# coop_assistant.net
KiCad netlist of a schematic drawn in EAGLE
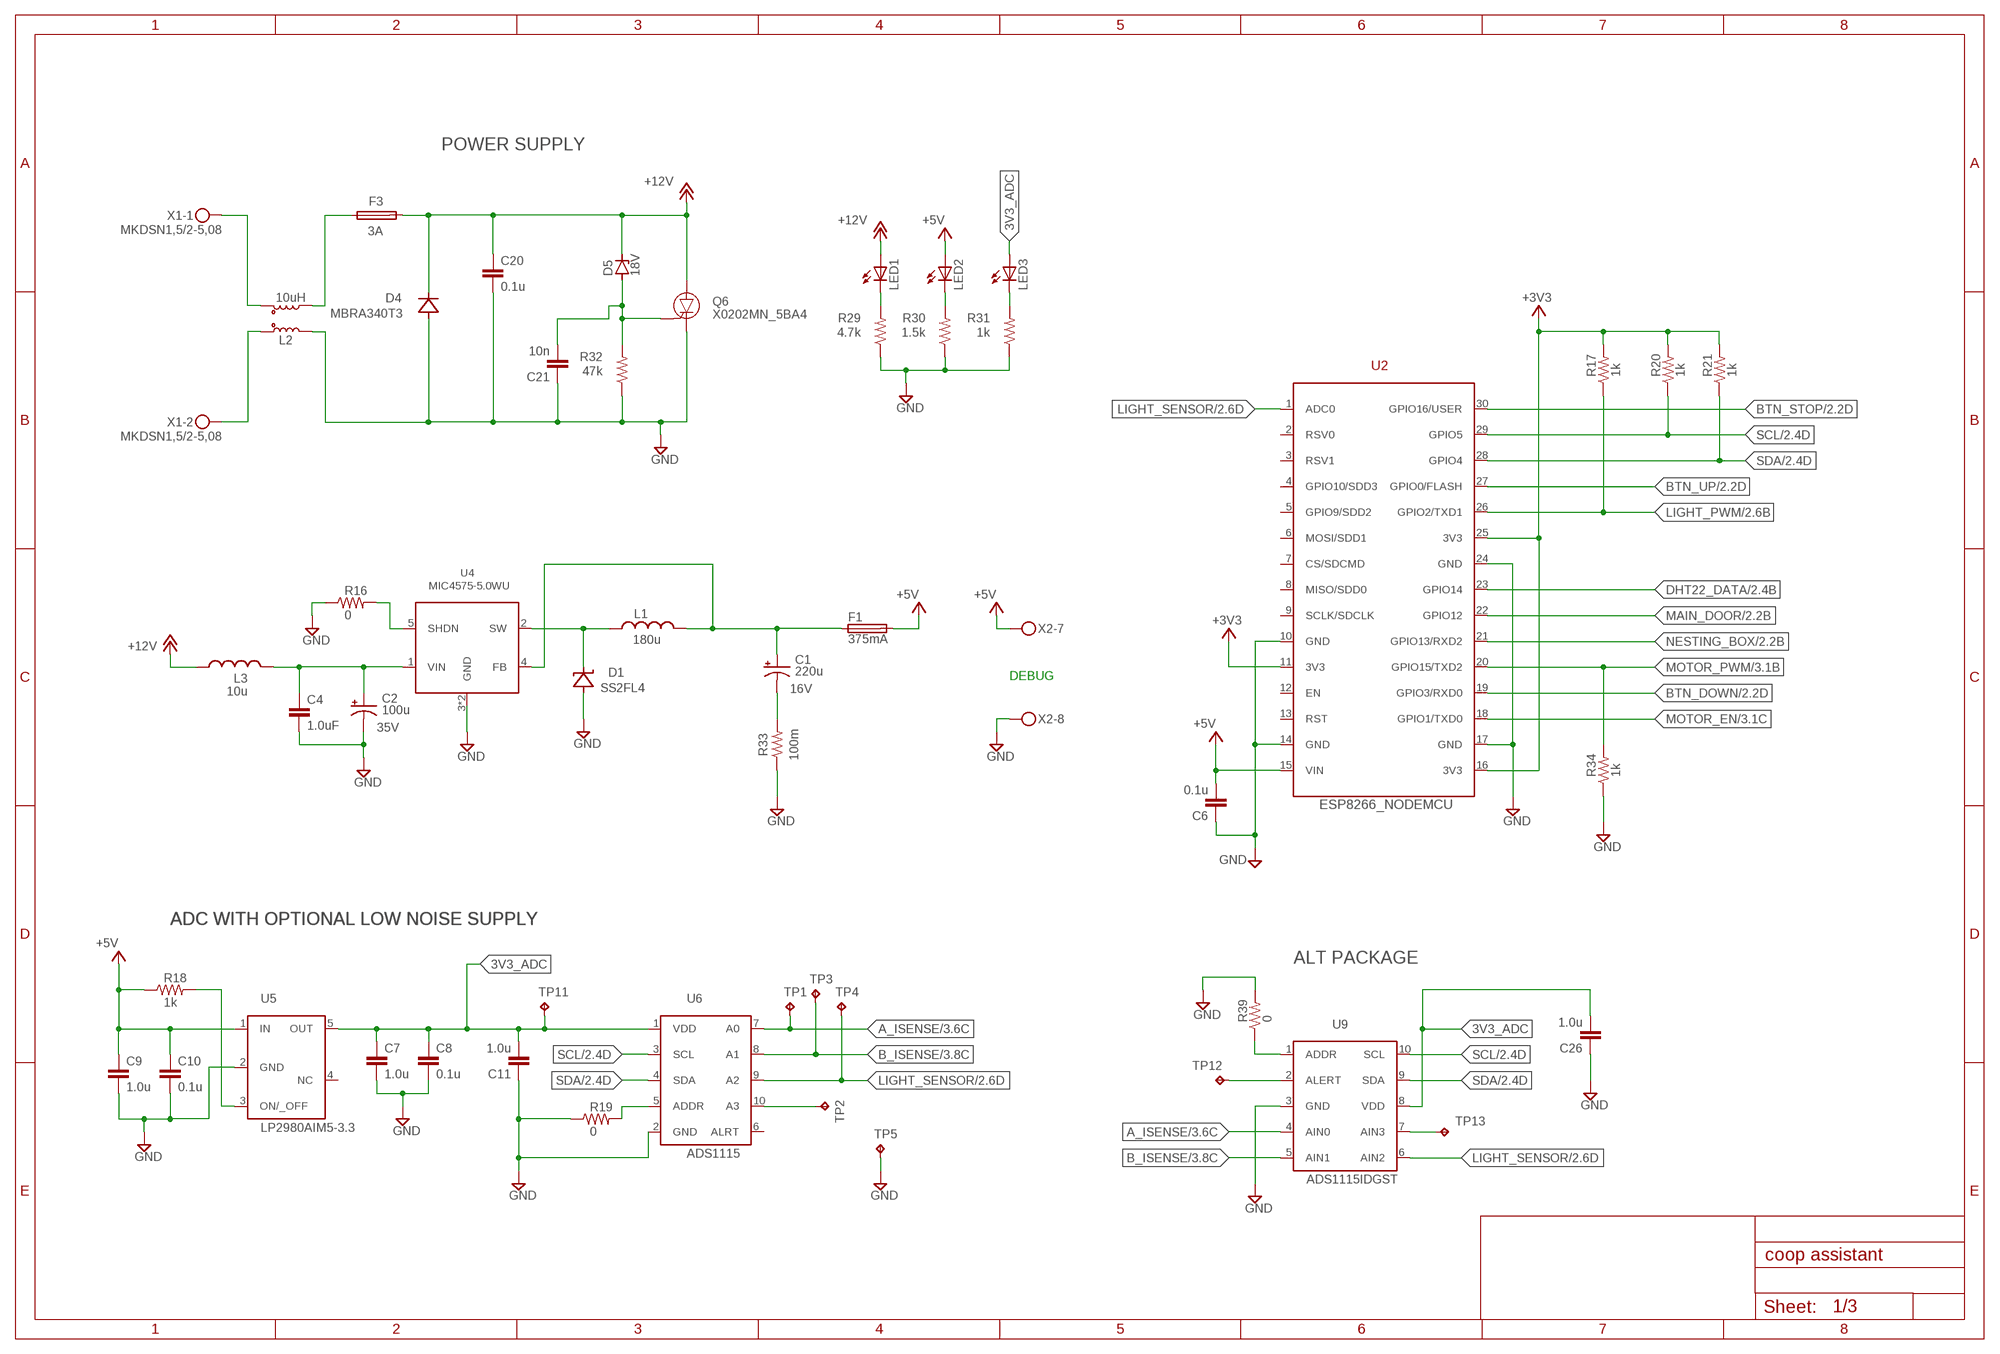
[diagram p0: schematic, sheet 1]
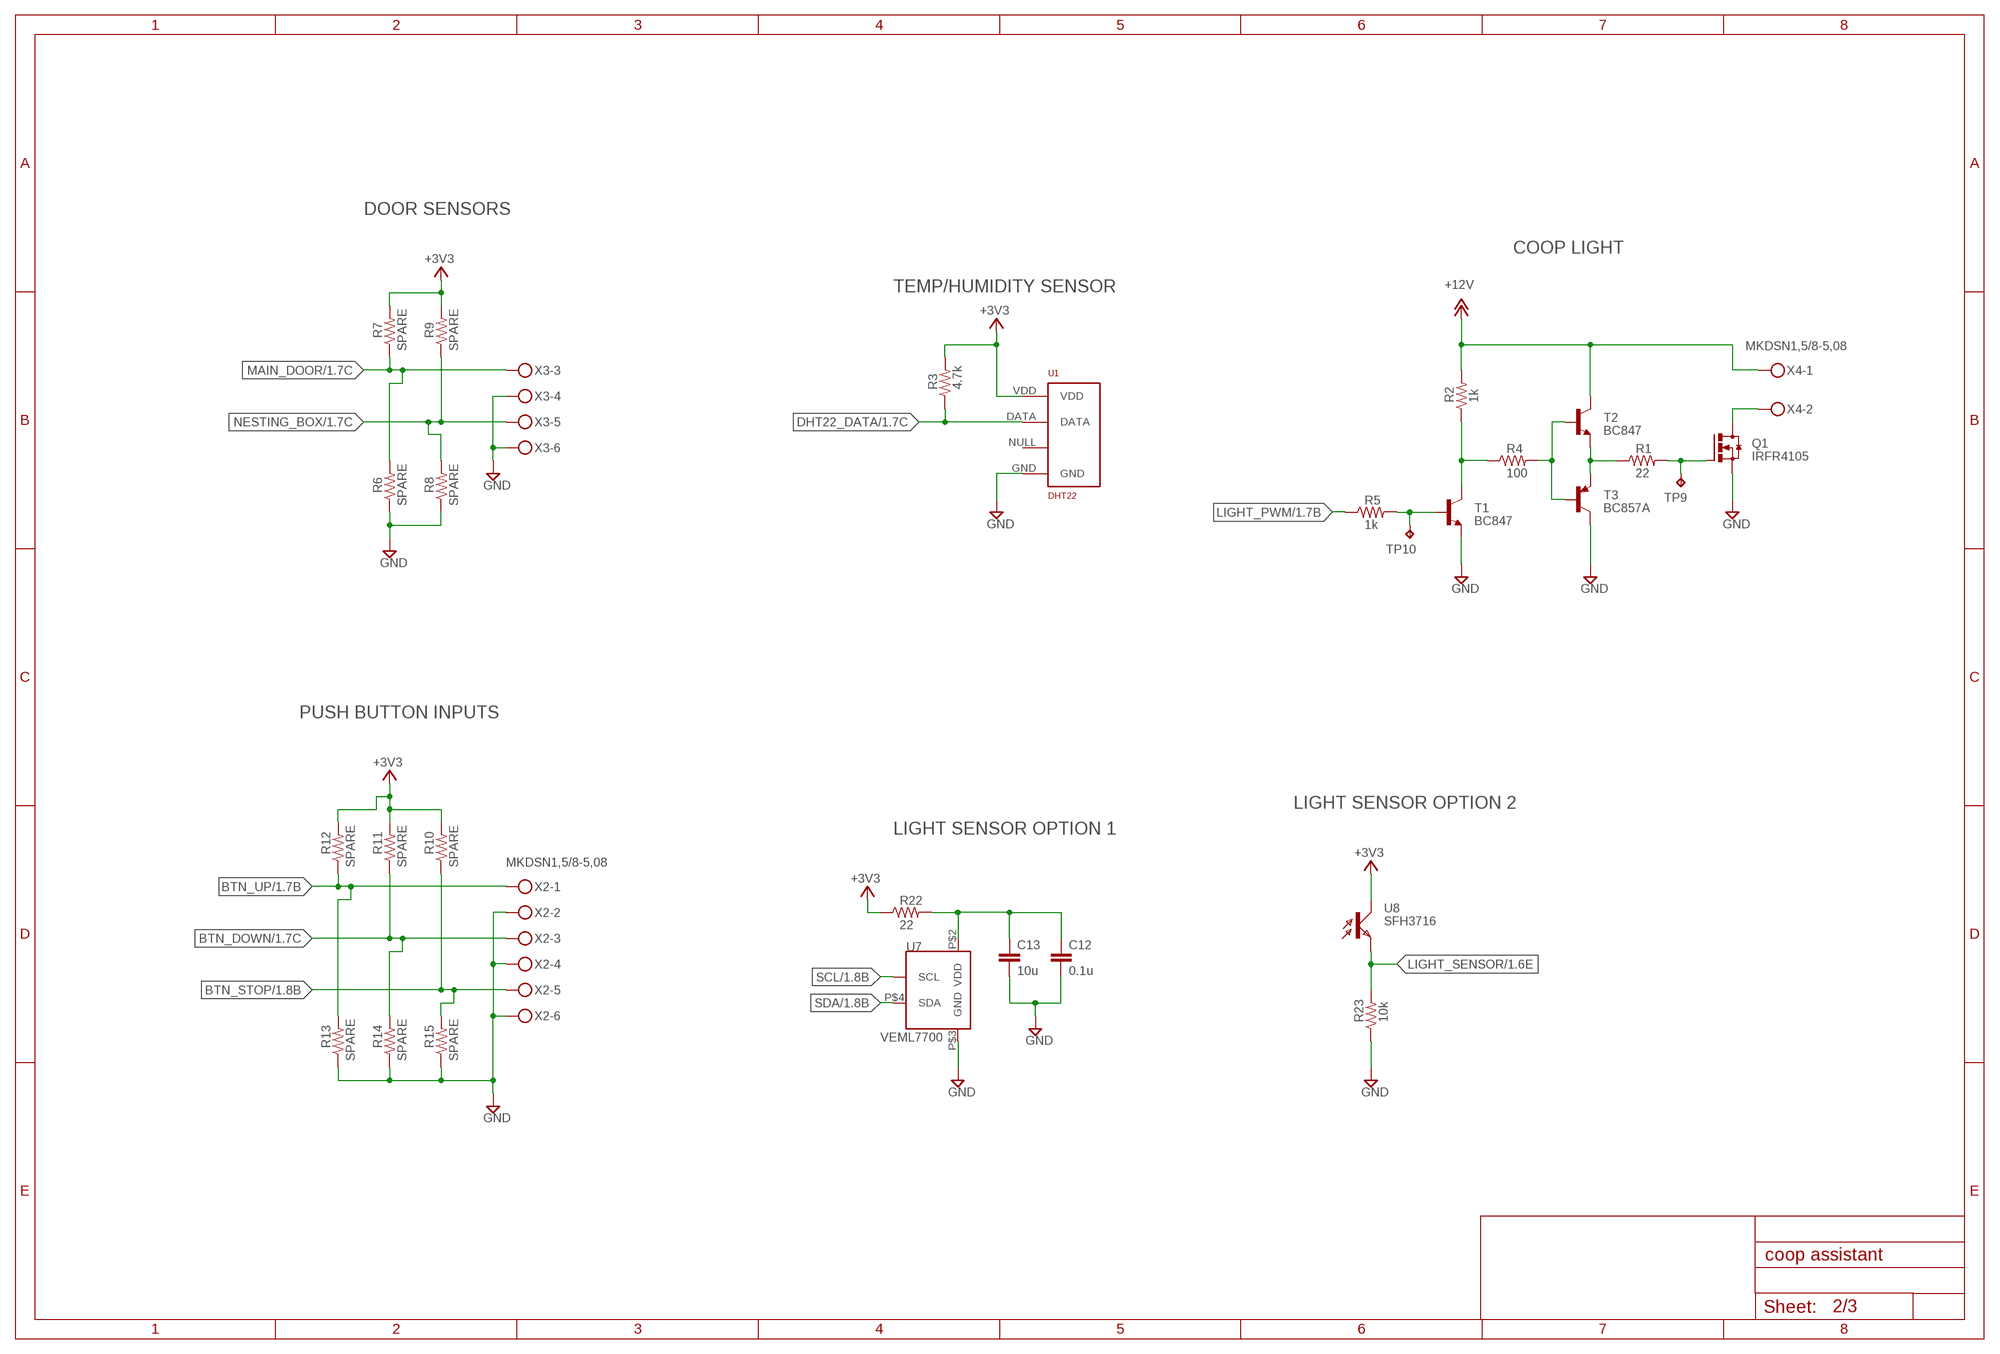
[diagram p1: schematic, sheet 2]
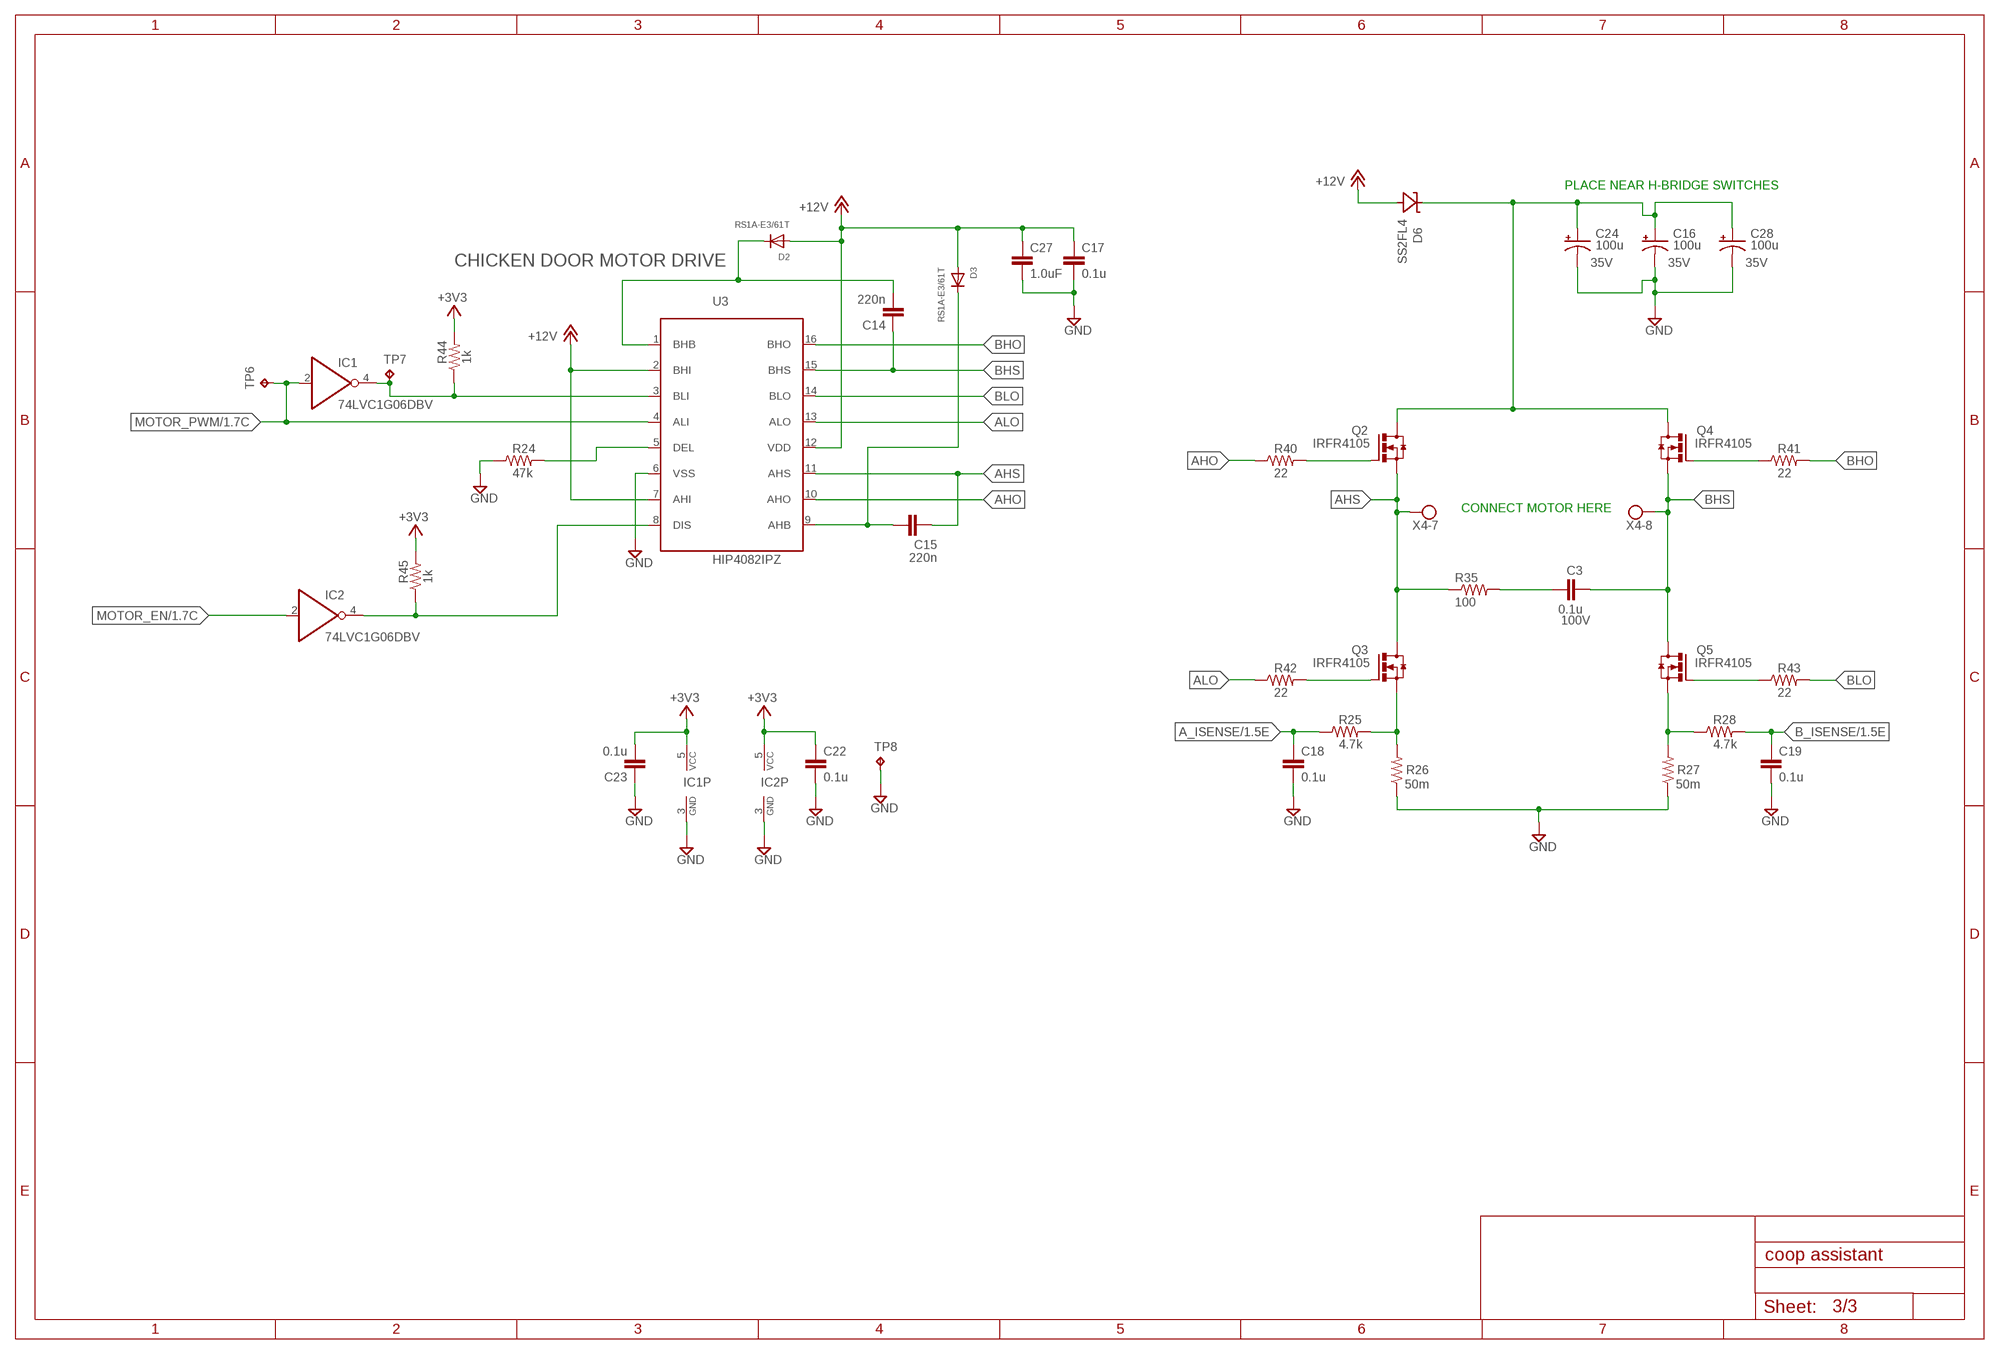
[diagram p2: schematic, sheet 3]

(export (version "E")
  (design (tool "Eeschema 10.0.6"))
  (components
    (comp (ref "C1")
      (value "220u")
      (footprint "eagle-import:CAPPRD250W50D630H800B")
      (fields (field (name "VOLTAGE") "16V"))
      (libsource (lib "eagle-import") (part "CPOLRAD6.3X8"))
    )
    (comp (ref "C2")
      (value "100u")
      (footprint "eagle-import:CAPPRD350W60D800H1200B")
      (fields (field (name "VOLTAGE") "35V"))
      (libsource (lib "eagle-import") (part "CPOLRAD8X12"))
    )
    (comp (ref "C4")
      (value "1.0uF")
      (footprint "eagle-import:0805")
      (libsource (lib "eagle-import") (part "1.0UF-0805-25V-10%"))
    )
    (comp (ref "C6")
      (value "0.1u")
      (footprint "eagle-import:0603")
      (libsource (lib "eagle-import") (part "1.0UF-0603-16V-10%"))
    )
    (comp (ref "C7")
      (value "1.0u")
      (footprint "eagle-import:0805")
      (libsource (lib "eagle-import") (part "1.0UF-0805-25V-10%"))
    )
    (comp (ref "C8")
      (value "0.1u")
      (footprint "eagle-import:0603")
      (libsource (lib "eagle-import") (part "1.0UF-0603-16V-10%"))
    )
    (comp (ref "C9")
      (value "1.0u")
      (footprint "eagle-import:0805")
      (libsource (lib "eagle-import") (part "1.0UF-0805-25V-10%"))
    )
    (comp (ref "C10")
      (value "0.1u")
      (footprint "eagle-import:0603")
      (libsource (lib "eagle-import") (part "1.0UF-0603-16V-10%"))
    )
    (comp (ref "C11")
      (value "1.0u")
      (footprint "eagle-import:0805")
      (libsource (lib "eagle-import") (part "1.0UF-0805-25V-10%"))
    )
    (comp (ref "C20")
      (value "0.1u")
      (footprint "eagle-import:C0805")
      (libsource (lib "eagle-import") (part "C-EUC0805"))
    )
    (comp (ref "C21")
      (value "10n")
      (footprint "eagle-import:C0805")
      (libsource (lib "eagle-import") (part "C-EUC0805"))
    )
    (comp (ref "C26")
      (value "1.0u")
      (footprint "eagle-import:0805")
      (libsource (lib "eagle-import") (part "1.0UF-0805-25V-10%"))
    )
    (comp (ref "D1")
      (value "SS2FL4")
      (footprint "eagle-import:SMF")
      (libsource (lib "eagle-import") (part "SS2FL4"))
    )
    (comp (ref "D4")
      (value "MBRA340T3")
      (footprint "eagle-import:SMA")
      (libsource (lib "eagle-import") (part "MBRA340T3"))
    )
    (comp (ref "D5")
      (value "18V")
      (footprint "eagle-import:SOT23")
      (libsource (lib "eagle-import") (part "ZENER-DIODESOT23"))
    )
    (comp (ref "F1")
      (value "375mA")
      (footprint "eagle-import:0603")
      (libsource (lib "eagle-import") (part "494SERIESFUSE"))
    )
    (comp (ref "F3")
      (value "3A")
      (footprint "eagle-import:FUSM9750X381N")
      (libsource (lib "eagle-import") (part "154_OMNIBLOKF154"))
    )
    (comp (ref "L1")
      (value "180u")
      (footprint "eagle-import:INDM120120X780N")
      (libsource (lib "eagle-import") (part "MSS1278"))
    )
    (comp (ref "L2")
      (value "10uH")
      (footprint "eagle-import:COILCRAFT_MSD1260")
      (libsource (lib "eagle-import") (part "COILCRAFT_MSD1260"))
    )
    (comp (ref "L3")
      (value "10u")
      (footprint "eagle-import:INDM120120X780N")
      (libsource (lib "eagle-import") (part "MSS1278"))
    )
    (comp (ref "LED1")
      (value "LEDCHIP-LED0805")
      (footprint "eagle-import:CHIP-LED0805")
      (libsource (lib "eagle-import") (part "LEDCHIP-LED0805"))
    )
    (comp (ref "LED2")
      (value "LEDCHIP-LED0805")
      (footprint "eagle-import:CHIP-LED0805")
      (libsource (lib "eagle-import") (part "LEDCHIP-LED0805"))
    )
    (comp (ref "LED3")
      (value "LEDCHIP-LED0805")
      (footprint "eagle-import:CHIP-LED0805")
      (libsource (lib "eagle-import") (part "LEDCHIP-LED0805"))
    )
    (comp (ref "Q6")
      (value "X0202MN_5BA4")
      (footprint "eagle-import:SOT-223")
      (fields
        (field (name "DIGIKEY_PARTNO") "497-2532-2-ND")
        (field (name "MANUFACTURER") "STMicroelectronics")
        (field (name "MPN") "X0202MN 5BA4")
        (field (name "CREATED_BY") "PCBLayout.com")
      )
      (libsource (lib "eagle-import") (part "X0202MN_5BA4"))
    )
    (comp (ref "R16")
      (value "0")
      (footprint "eagle-import:R0805")
      (libsource (lib "eagle-import") (part "R-US_R0805"))
    )
    (comp (ref "R17")
      (value "1k")
      (footprint "eagle-import:R0805")
      (libsource (lib "eagle-import") (part "R-US_R0805"))
    )
    (comp (ref "R18")
      (value "1k")
      (footprint "eagle-import:R0805")
      (libsource (lib "eagle-import") (part "R-US_R0805"))
    )
    (comp (ref "R19")
      (value "0")
      (footprint "eagle-import:R0805")
      (libsource (lib "eagle-import") (part "R-US_R0805"))
    )
    (comp (ref "R20")
      (value "1k")
      (footprint "eagle-import:R0805")
      (libsource (lib "eagle-import") (part "R-US_R0805"))
    )
    (comp (ref "R21")
      (value "1k")
      (footprint "eagle-import:R0805")
      (libsource (lib "eagle-import") (part "R-US_R0805"))
    )
    (comp (ref "R29")
      (value "4.7k")
      (footprint "eagle-import:R0805")
      (libsource (lib "eagle-import") (part "R-US_R0805"))
    )
    (comp (ref "R30")
      (value "1.5k")
      (footprint "eagle-import:R0805")
      (libsource (lib "eagle-import") (part "R-US_R0805"))
    )
    (comp (ref "R31")
      (value "1k")
      (footprint "eagle-import:R0805")
      (libsource (lib "eagle-import") (part "R-US_R0805"))
    )
    (comp (ref "R32")
      (value "47k")
      (footprint "eagle-import:R0805")
      (libsource (lib "eagle-import") (part "R-US_R0805"))
    )
    (comp (ref "R33")
      (value "100m")
      (footprint "eagle-import:RESC3216X70")
      (libsource (lib "eagle-import") (part "R-USCHIP-1206(3216-METRIC)_"))
    )
    (comp (ref "R34")
      (value "1k")
      (footprint "eagle-import:R0805")
      (libsource (lib "eagle-import") (part "R-US_R0805"))
    )
    (comp (ref "R39")
      (value "0")
      (footprint "eagle-import:R0805")
      (libsource (lib "eagle-import") (part "R-US_R0805"))
    )
    (comp (ref "TP1")
      (value "TPTP15SQ")
      (footprint "eagle-import:TP15SQ")
      (libsource (lib "eagle-import") (part "TPTP15SQ"))
    )
    (comp (ref "TP2")
      (value "TPTP15SQ")
      (footprint "eagle-import:TP15SQ")
      (libsource (lib "eagle-import") (part "TPTP15SQ"))
    )
    (comp (ref "TP3")
      (value "TPTP15SQ")
      (footprint "eagle-import:TP15SQ")
      (libsource (lib "eagle-import") (part "TPTP15SQ"))
    )
    (comp (ref "TP4")
      (value "TPTP15SQ")
      (footprint "eagle-import:TP15SQ")
      (libsource (lib "eagle-import") (part "TPTP15SQ"))
    )
    (comp (ref "TP5")
      (value "TPTP15SQ")
      (footprint "eagle-import:TP15SQ")
      (libsource (lib "eagle-import") (part "TPTP15SQ"))
    )
    (comp (ref "TP11")
      (value "TPTP15SQ")
      (footprint "eagle-import:TP15SQ")
      (libsource (lib "eagle-import") (part "TPTP15SQ"))
    )
    (comp (ref "TP12")
      (value "TPTP15SQ")
      (footprint "eagle-import:TP15SQ")
      (libsource (lib "eagle-import") (part "TPTP15SQ"))
    )
    (comp (ref "TP13")
      (value "TPTP15SQ")
      (footprint "eagle-import:TP15SQ")
      (libsource (lib "eagle-import") (part "TPTP15SQ"))
    )
    (comp (ref "U2")
      (value "ESP8266_NODEMCU")
      (footprint "eagle-import:NODEMCUESP8266")
      (libsource (lib "eagle-import") (part "ESP8266_NODEMCU"))
    )
    (comp (ref "U4")
      (value "MIC4575-5.0WU")
      (footprint "eagle-import:TO263-5")
      (libsource (lib "eagle-import") (part "MIC4575-5.0WU"))
    )
    (comp (ref "U5")
      (value "LP2980AIM5-3.3")
      (footprint "eagle-import:SOT23-5")
      (libsource (lib "eagle-import") (part "LP2980AIM5-3.3"))
    )
    (comp (ref "U6")
      (value "ADS1115")
      (footprint "eagle-import:HDRV10W64P254_1X10_2800X508X838B")
      (libsource (lib "eagle-import") (part "ADS1115"))
    )
    (comp (ref "U9")
      (value "ADS1115IDGST")
      (footprint "eagle-import:10VSSOP")
      (libsource (lib "eagle-import") (part "ADS1115IDGST"))
    )
    (comp (ref "X1")
      (value "MKDSN1,5/2-5,08")
      (footprint "eagle-import:MKDSN1,5_2-5,08")
      (libsource (lib "eagle-import") (part "MKDSN1,5/2-5,08"))
    )
    (comp (ref "X2")
      (value "MKDSN1,5/8-5,08")
      (footprint "eagle-import:MKDSN1,5_8-5,08")
      (libsource (lib "eagle-import") (part "MKDSN1,5/8-5,08"))
    )
    (comp (ref "C12")
      (value "0.1u")
      (footprint "eagle-import:0603")
      (libsource (lib "eagle-import") (part "1.0UF-0603-16V-10%"))
    )
    (comp (ref "C13")
      (value "10u")
      (footprint "eagle-import:0805")
      (libsource (lib "eagle-import") (part "1.0UF-0805-25V-(+80/-20%)"))
    )
    (comp (ref "Q1")
      (value "IRFR4105")
      (footprint "eagle-import:TO252")
      (libsource (lib "eagle-import") (part "IRFR4105"))
    )
    (comp (ref "R1")
      (value "22")
      (footprint "eagle-import:R0805")
      (libsource (lib "eagle-import") (part "R-US_R0805"))
    )
    (comp (ref "R2")
      (value "1k")
      (footprint "eagle-import:R0805")
      (libsource (lib "eagle-import") (part "R-US_R0805"))
    )
    (comp (ref "R3")
      (value "4.7k")
      (footprint "eagle-import:R0805")
      (libsource (lib "eagle-import") (part "R-US_R0805"))
    )
    (comp (ref "R4")
      (value "100")
      (footprint "eagle-import:R0805")
      (libsource (lib "eagle-import") (part "R-US_R0805"))
    )
    (comp (ref "R5")
      (value "1k")
      (footprint "eagle-import:R0805")
      (libsource (lib "eagle-import") (part "R-US_R0805"))
    )
    (comp (ref "R6")
      (value "SPARE")
      (footprint "eagle-import:R0805")
      (libsource (lib "eagle-import") (part "R-US_R0805"))
    )
    (comp (ref "R7")
      (value "SPARE")
      (footprint "eagle-import:R0805")
      (libsource (lib "eagle-import") (part "R-US_R0805"))
    )
    (comp (ref "R8")
      (value "SPARE")
      (footprint "eagle-import:R0805")
      (libsource (lib "eagle-import") (part "R-US_R0805"))
    )
    (comp (ref "R9")
      (value "SPARE")
      (footprint "eagle-import:R0805")
      (libsource (lib "eagle-import") (part "R-US_R0805"))
    )
    (comp (ref "R10")
      (value "SPARE")
      (footprint "eagle-import:R0805")
      (libsource (lib "eagle-import") (part "R-US_R0805"))
    )
    (comp (ref "R11")
      (value "SPARE")
      (footprint "eagle-import:R0805")
      (libsource (lib "eagle-import") (part "R-US_R0805"))
    )
    (comp (ref "R12")
      (value "SPARE")
      (footprint "eagle-import:R0805")
      (libsource (lib "eagle-import") (part "R-US_R0805"))
    )
    (comp (ref "R13")
      (value "SPARE")
      (footprint "eagle-import:R0805")
      (libsource (lib "eagle-import") (part "R-US_R0805"))
    )
    (comp (ref "R14")
      (value "SPARE")
      (footprint "eagle-import:R0805")
      (libsource (lib "eagle-import") (part "R-US_R0805"))
    )
    (comp (ref "R15")
      (value "SPARE")
      (footprint "eagle-import:R0805")
      (libsource (lib "eagle-import") (part "R-US_R0805"))
    )
    (comp (ref "R22")
      (value "22")
      (footprint "eagle-import:R0805")
      (libsource (lib "eagle-import") (part "R-US_R0805"))
    )
    (comp (ref "R23")
      (value "10k")
      (footprint "eagle-import:R0805")
      (libsource (lib "eagle-import") (part "R-US_R0805"))
    )
    (comp (ref "T1")
      (value "BC847")
      (footprint "eagle-import:SOT23")
      (libsource (lib "eagle-import") (part "BC847"))
    )
    (comp (ref "T2")
      (value "BC847")
      (footprint "eagle-import:SOT23")
      (libsource (lib "eagle-import") (part "BC847"))
    )
    (comp (ref "T3")
      (value "BC857A")
      (footprint "eagle-import:SOT23-BEC")
      (libsource (lib "eagle-import") (part "BC857A"))
    )
    (comp (ref "TP9")
      (value "TPTP15SQ")
      (footprint "eagle-import:TP15SQ")
      (libsource (lib "eagle-import") (part "TPTP15SQ"))
    )
    (comp (ref "TP10")
      (value "TPTP15SQ")
      (footprint "eagle-import:TP15SQ")
      (libsource (lib "eagle-import") (part "TPTP15SQ"))
    )
    (comp (ref "U1")
      (value "DHT22")
      (footprint "eagle-import:RHT03_DHT-22_RA")
      (libsource (lib "eagle-import") (part "RHT03_DHT-22_AM2302RA"))
    )
    (comp (ref "U7")
      (value "VEML7700")
      (footprint "eagle-import:VEML7700")
      (libsource (lib "eagle-import") (part "VEML7700"))
    )
    (comp (ref "U8")
      (value "SFH3716")
      (footprint "eagle-import:0805")
      (libsource (lib "eagle-import") (part "SFH3716"))
    )
    (comp (ref "X3")
      (value "MKDSN1,5/8-5,08")
      (footprint "eagle-import:MKDSN1,5_8-5,08")
      (libsource (lib "eagle-import") (part "MKDSN1,5/8-5,08"))
    )
    (comp (ref "X4")
      (value "MKDSN1,5/8-5,08")
      (footprint "eagle-import:MKDSN1,5_8-5,08")
      (libsource (lib "eagle-import") (part "MKDSN1,5/8-5,08"))
    )
    (comp (ref "C3")
      (value "0.1u")
      (footprint "eagle-import:C0805")
      (fields (field (name "VOLTAGE") "100V"))
      (libsource (lib "eagle-import") (part "C-EUC0805"))
    )
    (comp (ref "C14")
      (value "220n")
      (footprint "eagle-import:0805")
      (libsource (lib "eagle-import") (part "1.0UF-0805-25V-(+80/-20%)"))
    )
    (comp (ref "C15")
      (value "220n")
      (footprint "eagle-import:0805")
      (libsource (lib "eagle-import") (part "1.0UF-0805-25V-(+80/-20%)"))
    )
    (comp (ref "C16")
      (value "100u")
      (footprint "eagle-import:CAPPRD350W60D800H1200B")
      (fields (field (name "VOLTAGE") "35V"))
      (libsource (lib "eagle-import") (part "CPOLRAD8X12"))
    )
    (comp (ref "C17")
      (value "0.1u")
      (footprint "eagle-import:0603")
      (libsource (lib "eagle-import") (part "1.0UF-0603-16V-10%"))
    )
    (comp (ref "C18")
      (value "0.1u")
      (footprint "eagle-import:0603")
      (libsource (lib "eagle-import") (part "1.0UF-0603-16V-10%"))
    )
    (comp (ref "C19")
      (value "0.1u")
      (footprint "eagle-import:0603")
      (libsource (lib "eagle-import") (part "1.0UF-0603-16V-10%"))
    )
    (comp (ref "C22")
      (value "0.1u")
      (footprint "eagle-import:0603")
      (libsource (lib "eagle-import") (part "1.0UF-0603-16V-10%"))
    )
    (comp (ref "C23")
      (value "0.1u")
      (footprint "eagle-import:0603")
      (libsource (lib "eagle-import") (part "1.0UF-0603-16V-10%"))
    )
    (comp (ref "C24")
      (value "100u")
      (footprint "eagle-import:CAPPRD350W60D800H1200B")
      (fields (field (name "VOLTAGE") "35V"))
      (libsource (lib "eagle-import") (part "CPOLRAD8X12"))
    )
    (comp (ref "C27")
      (value "1.0uF")
      (footprint "eagle-import:0805")
      (libsource (lib "eagle-import") (part "1.0UF-0805-25V-10%"))
    )
    (comp (ref "C28")
      (value "100u")
      (footprint "eagle-import:CAPPRD350W60D800H1200B")
      (fields (field (name "VOLTAGE") "35V"))
      (libsource (lib "eagle-import") (part "CPOLRAD8X12"))
    )
    (comp (ref "D2")
      (value "RS1A-E3/61T")
      (footprint "eagle-import:SMADIODE")
      (libsource (lib "eagle-import") (part "DIODESMA"))
    )
    (comp (ref "D3")
      (value "RS1A-E3/61T")
      (footprint "eagle-import:SMADIODE")
      (libsource (lib "eagle-import") (part "DIODESMA"))
    )
    (comp (ref "D6")
      (value "SS2FL4")
      (footprint "eagle-import:SMF")
      (libsource (lib "eagle-import") (part "SS2FL4"))
    )
    (comp (ref "IC1")
      (value "74LVC1G06DBV")
      (footprint "eagle-import:SOT23-5")
      (libsource (lib "eagle-import") (part "741G06DBVLVC"))
    )
    (comp (ref "IC2")
      (value "74LVC1G06DBV")
      (footprint "eagle-import:SOT23-5")
      (libsource (lib "eagle-import") (part "741G06DBVLVC"))
    )
    (comp (ref "Q2")
      (value "IRFR4105")
      (footprint "eagle-import:TO252")
      (libsource (lib "eagle-import") (part "IRFR4105"))
    )
    (comp (ref "Q3")
      (value "IRFR4105")
      (footprint "eagle-import:TO252")
      (libsource (lib "eagle-import") (part "IRFR4105"))
    )
    (comp (ref "Q4")
      (value "IRFR4105")
      (footprint "eagle-import:TO252")
      (libsource (lib "eagle-import") (part "IRFR4105"))
    )
    (comp (ref "Q5")
      (value "IRFR4105")
      (footprint "eagle-import:TO252")
      (libsource (lib "eagle-import") (part "IRFR4105"))
    )
    (comp (ref "R24")
      (value "47k")
      (footprint "eagle-import:R0805")
      (libsource (lib "eagle-import") (part "R-US_R0805"))
    )
    (comp (ref "R25")
      (value "4.7k")
      (footprint "eagle-import:R0805")
      (libsource (lib "eagle-import") (part "R-US_R0805"))
    )
    (comp (ref "R26")
      (value "50m")
      (footprint "eagle-import:R2512")
      (libsource (lib "eagle-import") (part "R-US_R2512"))
    )
    (comp (ref "R27")
      (value "50m")
      (footprint "eagle-import:R2512")
      (libsource (lib "eagle-import") (part "R-US_R2512"))
    )
    (comp (ref "R28")
      (value "4.7k")
      (footprint "eagle-import:R0805")
      (libsource (lib "eagle-import") (part "R-US_R0805"))
    )
    (comp (ref "R35")
      (value "100")
      (footprint "eagle-import:R2512")
      (libsource (lib "eagle-import") (part "R-US_R2512"))
    )
    (comp (ref "R40")
      (value "22")
      (footprint "eagle-import:R0805")
      (libsource (lib "eagle-import") (part "R-US_R0805"))
    )
    (comp (ref "R41")
      (value "22")
      (footprint "eagle-import:R0805")
      (libsource (lib "eagle-import") (part "R-US_R0805"))
    )
    (comp (ref "R42")
      (value "22")
      (footprint "eagle-import:R0805")
      (libsource (lib "eagle-import") (part "R-US_R0805"))
    )
    (comp (ref "R43")
      (value "22")
      (footprint "eagle-import:R0805")
      (libsource (lib "eagle-import") (part "R-US_R0805"))
    )
    (comp (ref "R44")
      (value "1k")
      (footprint "eagle-import:R0805")
      (libsource (lib "eagle-import") (part "R-US_R0805"))
    )
    (comp (ref "R45")
      (value "1k")
      (footprint "eagle-import:R0805")
      (libsource (lib "eagle-import") (part "R-US_R0805"))
    )
    (comp (ref "TP6")
      (value "TPTP15SQ")
      (footprint "eagle-import:TP15SQ")
      (libsource (lib "eagle-import") (part "TPTP15SQ"))
    )
    (comp (ref "TP7")
      (value "TPTP15SQ")
      (footprint "eagle-import:TP15SQ")
      (libsource (lib "eagle-import") (part "TPTP15SQ"))
    )
    (comp (ref "TP8")
      (value "TPTP15SQ")
      (footprint "eagle-import:TP15SQ")
      (libsource (lib "eagle-import") (part "TPTP15SQ"))
    )
    (comp (ref "U3")
      (value "HIP4082IPZ")
      (footprint "eagle-import:DIP762W53P254L1969H508Q16B")
      (libsource (lib "eagle-import") (part "HIP4082IPZ"))
    )
  )
  (nets
    (net (code "1") (name "+3V3") (class "Default")
      (node (ref "C22") (pin "1") (pinfunction "1_1") (pintype "passive"))
      (node (ref "C23") (pin "2") (pinfunction "2_2") (pintype "passive"))
      (node (ref "IC1") (pin "5") (pinfunction "VCC_5") (pintype "power_in"))
      (node (ref "IC2") (pin "5") (pinfunction "VCC_5") (pintype "power_in"))
      (node (ref "R10") (pin "2") (pinfunction "2_2") (pintype "passive"))
      (node (ref "R11") (pin "2") (pinfunction "2_2") (pintype "passive"))
      (node (ref "R12") (pin "2") (pinfunction "2_2") (pintype "passive"))
      (node (ref "R17") (pin "2") (pinfunction "2_2") (pintype "passive"))
      (node (ref "R20") (pin "2") (pinfunction "2_2") (pintype "passive"))
      (node (ref "R21") (pin "2") (pinfunction "2_2") (pintype "passive"))
      (node (ref "R22") (pin "1") (pinfunction "1_1") (pintype "passive"))
      (node (ref "R3") (pin "2") (pinfunction "2_2") (pintype "passive"))
      (node (ref "R44") (pin "2") (pinfunction "2_2") (pintype "passive"))
      (node (ref "R45") (pin "2") (pinfunction "2_2") (pintype "passive"))
      (node (ref "R7") (pin "2") (pinfunction "2_2") (pintype "passive"))
      (node (ref "R9") (pin "2") (pinfunction "2_2") (pintype "passive"))
      (node (ref "U1") (pin "VDD") (pinfunction "VDD_VDD") (pintype "power_in"))
      (node (ref "U2") (pin "11") (pinfunction "3V3_11") (pintype "power_in"))
      (node (ref "U2") (pin "16") (pinfunction "3V3_16") (pintype "power_in"))
      (node (ref "U2") (pin "25") (pinfunction "3V3_25") (pintype "power_in"))
      (node (ref "U8") (pin "1") (pinfunction "C_1") (pintype "passive"))
    )
    (net (code "2") (name "+5V") (class "Default")
      (node (ref "C10") (pin "1") (pinfunction "1_1") (pintype "passive"))
      (node (ref "C6") (pin "2") (pinfunction "2_2") (pintype "passive"))
      (node (ref "C9") (pin "1") (pinfunction "1_1") (pintype "passive"))
      (node (ref "F1") (pin "2") (pinfunction "2_2") (pintype "passive"))
      (node (ref "LED2") (pin "A") (pinfunction "A_A") (pintype "passive"))
      (node (ref "R18") (pin "1") (pinfunction "1_1") (pintype "passive"))
      (node (ref "U2") (pin "15") (pinfunction "VIN_15") (pintype "power_in"))
      (node (ref "U5") (pin "1") (pinfunction "IN_1") (pintype "power_in"))
      (node (ref "X2") (pin "7") (pinfunction "KL_7") (pintype "passive"))
    )
    (net (code "3") (name "+12V") (class "Default")
      (node (ref "C17") (pin "1") (pinfunction "1_1") (pintype "passive"))
      (node (ref "C20") (pin "1") (pinfunction "1_1") (pintype "passive"))
      (node (ref "C27") (pin "1") (pinfunction "1_1") (pintype "passive"))
      (node (ref "D2") (pin "A") (pinfunction "A_A") (pintype "passive"))
      (node (ref "D3") (pin "A") (pinfunction "A_A") (pintype "passive"))
      (node (ref "D4") (pin "C") (pinfunction "C_C") (pintype "passive"))
      (node (ref "D5") (pin "3") (pinfunction "C_3") (pintype "passive"))
      (node (ref "D6") (pin "A") (pinfunction "A_A") (pintype "passive"))
      (node (ref "F3") (pin "2") (pinfunction "2_2") (pintype "passive"))
      (node (ref "L3") (pin "1") (pinfunction "1_1") (pintype "passive"))
      (node (ref "LED1") (pin "A") (pinfunction "A_A") (pintype "passive"))
      (node (ref "Q6") (pin "A") (pinfunction "A_A") (pintype "passive"))
      (node (ref "Q6") (pin "A1") (pinfunction "A_A1") (pintype "passive"))
      (node (ref "R2") (pin "2") (pinfunction "2_2") (pintype "passive"))
      (node (ref "T2") (pin "3") (pinfunction "C_3") (pintype "passive"))
      (node (ref "U3") (pin "12") (pinfunction "VDD_12") (pintype "power_in"))
      (node (ref "U3") (pin "2") (pinfunction "BHI_2") (pintype "bidirectional"))
      (node (ref "U3") (pin "7") (pinfunction "AHI_7") (pintype "bidirectional"))
      (node (ref "X4") (pin "1") (pinfunction "KL_1") (pintype "passive"))
    )
    (net (code "4") (name "3V3_ADC") (class "Default")
      (node (ref "C11") (pin "2") (pinfunction "2_2") (pintype "passive"))
      (node (ref "C26") (pin "2") (pinfunction "2_2") (pintype "passive"))
      (node (ref "C7") (pin "1") (pinfunction "1_1") (pintype "passive"))
      (node (ref "C8") (pin "1") (pinfunction "1_1") (pintype "passive"))
      (node (ref "LED3") (pin "A") (pinfunction "A_A") (pintype "passive"))
      (node (ref "TP11") (pin "TP") (pinfunction "TP_TP") (pintype "input"))
      (node (ref "U5") (pin "5") (pinfunction "OUT_5") (pintype "power_in"))
      (node (ref "U6") (pin "1") (pinfunction "VDD_1") (pintype "power_in"))
      (node (ref "U9") (pin "8") (pinfunction "VDD_8") (pintype "power_in"))
    )
    (net (code "5") (name "AHO") (class "Default")
      (node (ref "R40") (pin "1") (pinfunction "1_1") (pintype "passive"))
      (node (ref "U3") (pin "10") (pinfunction "AHO_10") (pintype "bidirectional"))
    )
    (net (code "6") (name "AHS") (class "Default")
      (node (ref "C15") (pin "2") (pinfunction "2_2") (pintype "passive"))
      (node (ref "Q2") (pin "2") (pinfunction "S_2") (pintype "passive"))
      (node (ref "Q3") (pin "3") (pinfunction "D_3") (pintype "passive"))
      (node (ref "R35") (pin "1") (pinfunction "1_1") (pintype "passive"))
      (node (ref "U3") (pin "11") (pinfunction "AHS_11") (pintype "bidirectional"))
      (node (ref "X4") (pin "7") (pinfunction "KL_7") (pintype "passive"))
    )
    (net (code "7") (name "ALO") (class "Default")
      (node (ref "R42") (pin "1") (pinfunction "1_1") (pintype "passive"))
      (node (ref "U3") (pin "13") (pinfunction "ALO_13") (pintype "bidirectional"))
    )
    (net (code "8") (name "A_ISENSE") (class "Default")
      (node (ref "C18") (pin "1") (pinfunction "1_1") (pintype "passive"))
      (node (ref "R25") (pin "1") (pinfunction "1_1") (pintype "passive"))
      (node (ref "TP1") (pin "TP") (pinfunction "TP_TP") (pintype "input"))
      (node (ref "U6") (pin "7") (pinfunction "A0_7") (pintype "input"))
      (node (ref "U9") (pin "4") (pinfunction "AIN0_4") (pintype "input"))
    )
    (net (code "9") (name "BHO") (class "Default")
      (node (ref "R41") (pin "2") (pinfunction "2_2") (pintype "passive"))
      (node (ref "U3") (pin "16") (pinfunction "BHO_16") (pintype "bidirectional"))
    )
    (net (code "10") (name "BHS") (class "Default")
      (node (ref "C14") (pin "1") (pinfunction "1_1") (pintype "passive"))
      (node (ref "C3") (pin "2") (pinfunction "2_2") (pintype "passive"))
      (node (ref "Q4") (pin "2") (pinfunction "S_2") (pintype "passive"))
      (node (ref "Q5") (pin "3") (pinfunction "D_3") (pintype "passive"))
      (node (ref "U3") (pin "15") (pinfunction "BHS_15") (pintype "bidirectional"))
      (node (ref "X4") (pin "8") (pinfunction "KL_8") (pintype "passive"))
    )
    (net (code "11") (name "BLO") (class "Default")
      (node (ref "R43") (pin "2") (pinfunction "2_2") (pintype "passive"))
      (node (ref "U3") (pin "14") (pinfunction "BLO_14") (pintype "bidirectional"))
    )
    (net (code "12") (name "BTN_DOWN") (class "Default")
      (node (ref "R11") (pin "1") (pinfunction "1_1") (pintype "passive"))
      (node (ref "R14") (pin "2") (pinfunction "2_2") (pintype "passive"))
      (node (ref "U2") (pin "19") (pinfunction "GPIO3/RXD0_19") (pintype "bidirectional"))
      (node (ref "X2") (pin "3") (pinfunction "KL_3") (pintype "passive"))
    )
    (net (code "13") (name "BTN_STOP") (class "Default")
      (node (ref "R10") (pin "1") (pinfunction "1_1") (pintype "passive"))
      (node (ref "R15") (pin "2") (pinfunction "2_2") (pintype "passive"))
      (node (ref "U2") (pin "30") (pinfunction "GPIO16/USER_30") (pintype "bidirectional"))
      (node (ref "X2") (pin "5") (pinfunction "KL_5") (pintype "passive"))
    )
    (net (code "14") (name "BTN_UP") (class "Default")
      (node (ref "R12") (pin "1") (pinfunction "1_1") (pintype "passive"))
      (node (ref "R13") (pin "2") (pinfunction "2_2") (pintype "passive"))
      (node (ref "U2") (pin "27") (pinfunction "GPIO0/FLASH_27") (pintype "bidirectional"))
      (node (ref "X2") (pin "1") (pinfunction "KL_1") (pintype "passive"))
    )
    (net (code "15") (name "B_ISENSE") (class "Default")
      (node (ref "C19") (pin "1") (pinfunction "1_1") (pintype "passive"))
      (node (ref "R28") (pin "2") (pinfunction "2_2") (pintype "passive"))
      (node (ref "TP3") (pin "TP") (pinfunction "TP_TP") (pintype "input"))
      (node (ref "U6") (pin "8") (pinfunction "A1_8") (pintype "input"))
      (node (ref "U9") (pin "5") (pinfunction "AIN1_5") (pintype "input"))
    )
    (net (code "16") (name "DHT22_DATA") (class "Default")
      (node (ref "R3") (pin "1") (pinfunction "1_1") (pintype "passive"))
      (node (ref "U1") (pin "DATA") (pinfunction "DATA_DATA") (pintype "bidirectional"))
      (node (ref "U2") (pin "23") (pinfunction "GPIO14_23") (pintype "bidirectional"))
    )
    (net (code "17") (name "GND") (class "Default")
      (node (ref "C10") (pin "2") (pinfunction "2_2") (pintype "passive"))
      (node (ref "C11") (pin "1") (pinfunction "1_1") (pintype "passive"))
      (node (ref "C12") (pin "2") (pinfunction "2_2") (pintype "passive"))
      (node (ref "C13") (pin "2") (pinfunction "2_2") (pintype "passive"))
      (node (ref "C16") (pin "NEG") (pinfunction "-_NEG") (pintype "passive"))
      (node (ref "C17") (pin "2") (pinfunction "2_2") (pintype "passive"))
      (node (ref "C18") (pin "2") (pinfunction "2_2") (pintype "passive"))
      (node (ref "C19") (pin "2") (pinfunction "2_2") (pintype "passive"))
      (node (ref "C2") (pin "NEG") (pinfunction "-_NEG") (pintype "passive"))
      (node (ref "C20") (pin "2") (pinfunction "2_2") (pintype "passive"))
      (node (ref "C21") (pin "1") (pinfunction "1_1") (pintype "passive"))
      (node (ref "C22") (pin "2") (pinfunction "2_2") (pintype "passive"))
      (node (ref "C23") (pin "1") (pinfunction "1_1") (pintype "passive"))
      (node (ref "C24") (pin "NEG") (pinfunction "-_NEG") (pintype "passive"))
      (node (ref "C26") (pin "1") (pinfunction "1_1") (pintype "passive"))
      (node (ref "C27") (pin "2") (pinfunction "2_2") (pintype "passive"))
      (node (ref "C28") (pin "NEG") (pinfunction "-_NEG") (pintype "passive"))
      (node (ref "C4") (pin "2") (pinfunction "2_2") (pintype "passive"))
      (node (ref "C6") (pin "1") (pinfunction "1_1") (pintype "passive"))
      (node (ref "C7") (pin "2") (pinfunction "2_2") (pintype "passive"))
      (node (ref "C8") (pin "2") (pinfunction "2_2") (pintype "passive"))
      (node (ref "C9") (pin "2") (pinfunction "2_2") (pintype "passive"))
      (node (ref "D1") (pin "A") (pinfunction "A_A") (pintype "passive"))
      (node (ref "D4") (pin "A") (pinfunction "A_A") (pintype "passive"))
      (node (ref "IC1") (pin "3") (pinfunction "GND_3") (pintype "power_in"))
      (node (ref "IC2") (pin "3") (pinfunction "GND_3") (pintype "power_in"))
      (node (ref "L2") (pin "4") (pinfunction "4_4") (pintype "passive"))
      (node (ref "Q1") (pin "2") (pinfunction "S_2") (pintype "passive"))
      (node (ref "Q6") (pin "K") (pinfunction "K_K") (pintype "passive"))
      (node (ref "R13") (pin "1") (pinfunction "1_1") (pintype "passive"))
      (node (ref "R14") (pin "1") (pinfunction "1_1") (pintype "passive"))
      (node (ref "R15") (pin "1") (pinfunction "1_1") (pintype "passive"))
      (node (ref "R16") (pin "1") (pinfunction "1_1") (pintype "passive"))
      (node (ref "R19") (pin "1") (pinfunction "1_1") (pintype "passive"))
      (node (ref "R23") (pin "1") (pinfunction "1_1") (pintype "passive"))
      (node (ref "R24") (pin "1") (pinfunction "1_1") (pintype "passive"))
      (node (ref "R26") (pin "1") (pinfunction "1_1") (pintype "passive"))
      (node (ref "R27") (pin "1") (pinfunction "1_1") (pintype "passive"))
      (node (ref "R29") (pin "1") (pinfunction "1_1") (pintype "passive"))
      (node (ref "R30") (pin "1") (pinfunction "1_1") (pintype "passive"))
      (node (ref "R31") (pin "1") (pinfunction "1_1") (pintype "passive"))
      (node (ref "R32") (pin "1") (pinfunction "1_1") (pintype "passive"))
      (node (ref "R33") (pin "1") (pinfunction "1_1") (pintype "passive"))
      (node (ref "R34") (pin "1") (pinfunction "1_1") (pintype "passive"))
      (node (ref "R39") (pin "2") (pinfunction "2_2") (pintype "passive"))
      (node (ref "R6") (pin "1") (pinfunction "1_1") (pintype "passive"))
      (node (ref "R8") (pin "1") (pinfunction "1_1") (pintype "passive"))
      (node (ref "T1") (pin "2") (pinfunction "E_2") (pintype "passive"))
      (node (ref "T3") (pin "C") (pinfunction "C_C") (pintype "passive"))
      (node (ref "TP5") (pin "TP") (pinfunction "TP_TP") (pintype "input"))
      (node (ref "TP8") (pin "TP") (pinfunction "TP_TP") (pintype "input"))
      (node (ref "U1") (pin "GND") (pinfunction "GND_GND") (pintype "power_in"))
      (node (ref "U2") (pin "10") (pinfunction "GND_10") (pintype "power_in"))
      (node (ref "U2") (pin "14") (pinfunction "GND_14") (pintype "power_in"))
      (node (ref "U2") (pin "17") (pinfunction "GND_17") (pintype "power_in"))
      (node (ref "U2") (pin "24") (pinfunction "GND_24") (pintype "power_in"))
      (node (ref "U3") (pin "6") (pinfunction "VSS_6") (pintype "power_in"))
      (node (ref "U4") (pin "3") (pinfunction "GND_3") (pintype "power_in"))
      (node (ref "U4") (pin "6") (pinfunction "GND_6") (pintype "power_in"))
      (node (ref "U5") (pin "2") (pinfunction "GND_2") (pintype "power_in"))
      (node (ref "U6") (pin "2") (pinfunction "GND_2") (pintype "power_in"))
      (node (ref "U7") (pin "P$3") (pinfunction "GND_P$3") (pintype "bidirectional"))
      (node (ref "U9") (pin "3") (pinfunction "GND_3") (pintype "power_in"))
      (node (ref "X2") (pin "2") (pinfunction "KL_2") (pintype "passive"))
      (node (ref "X2") (pin "4") (pinfunction "KL_4") (pintype "passive"))
      (node (ref "X2") (pin "6") (pinfunction "KL_6") (pintype "passive"))
      (node (ref "X2") (pin "8") (pinfunction "KL_8") (pintype "passive"))
      (node (ref "X3") (pin "4") (pinfunction "KL_4") (pintype "passive"))
      (node (ref "X3") (pin "6") (pinfunction "KL_6") (pintype "passive"))
    )
    (net (code "18") (name "LIGHT_PWM") (class "Default")
      (node (ref "R17") (pin "1") (pinfunction "1_1") (pintype "passive"))
      (node (ref "R5") (pin "1") (pinfunction "1_1") (pintype "passive"))
      (node (ref "U2") (pin "26") (pinfunction "GPIO2/TXD1_26") (pintype "bidirectional"))
    )
    (net (code "19") (name "LIGHT_SENSOR") (class "Default")
      (node (ref "R23") (pin "2") (pinfunction "2_2") (pintype "passive"))
      (node (ref "TP4") (pin "TP") (pinfunction "TP_TP") (pintype "input"))
      (node (ref "U2") (pin "1") (pinfunction "ADC0_1") (pintype "bidirectional"))
      (node (ref "U6") (pin "9") (pinfunction "A2_9") (pintype "input"))
      (node (ref "U8") (pin "2") (pinfunction "E_2") (pintype "passive"))
      (node (ref "U9") (pin "6") (pinfunction "AIN2_6") (pintype "input"))
    )
    (net (code "20") (name "MAIN_DOOR") (class "Default")
      (node (ref "R6") (pin "2") (pinfunction "2_2") (pintype "passive"))
      (node (ref "R7") (pin "1") (pinfunction "1_1") (pintype "passive"))
      (node (ref "U2") (pin "22") (pinfunction "GPIO12_22") (pintype "bidirectional"))
      (node (ref "X3") (pin "3") (pinfunction "KL_3") (pintype "passive"))
    )
    (net (code "21") (name "MOTOR_EN") (class "Default")
      (node (ref "IC2") (pin "2") (pinfunction "I_2") (pintype "input"))
      (node (ref "U2") (pin "18") (pinfunction "GPIO1/TXD0_18") (pintype "bidirectional"))
    )
    (net (code "22") (name "MOTOR_PWM") (class "Default")
      (node (ref "IC1") (pin "2") (pinfunction "I_2") (pintype "input"))
      (node (ref "R34") (pin "2") (pinfunction "2_2") (pintype "passive"))
      (node (ref "TP6") (pin "TP") (pinfunction "TP_TP") (pintype "input"))
      (node (ref "U2") (pin "20") (pinfunction "GPIO15/TXD2_20") (pintype "bidirectional"))
      (node (ref "U3") (pin "4") (pinfunction "ALI_4") (pintype "bidirectional"))
    )
    (net (code "23") (name "NESTING_BOX") (class "Default")
      (node (ref "R8") (pin "2") (pinfunction "2_2") (pintype "passive"))
      (node (ref "R9") (pin "1") (pinfunction "1_1") (pintype "passive"))
      (node (ref "U2") (pin "21") (pinfunction "GPIO13/RXD2_21") (pintype "bidirectional"))
      (node (ref "X3") (pin "5") (pinfunction "KL_5") (pintype "passive"))
    )
    (net (code "24") (name "Net-(C1-+)") (class "Default")
      (node (ref "C1") (pin "POS") (pinfunction "+_POS") (pintype "passive"))
      (node (ref "F1") (pin "1") (pinfunction "1_1") (pintype "passive"))
      (node (ref "L1") (pin "2") (pinfunction "2_2") (pintype "passive"))
      (node (ref "U4") (pin "4") (pinfunction "FB_4") (pintype "power_in"))
    )
    (net (code "25") (name "Net-(C1--)") (class "Default")
      (node (ref "C1") (pin "NEG") (pinfunction "-_NEG") (pintype "passive"))
      (node (ref "R33") (pin "2") (pinfunction "2_2") (pintype "passive"))
    )
    (net (code "26") (name "Net-(C2-+)") (class "Default")
      (node (ref "C2") (pin "POS") (pinfunction "+_POS") (pintype "passive"))
      (node (ref "C4") (pin "1") (pinfunction "1_1") (pintype "passive"))
      (node (ref "L3") (pin "2") (pinfunction "2_2") (pintype "passive"))
      (node (ref "U4") (pin "1") (pinfunction "VIN_1") (pintype "power_in"))
    )
    (net (code "27") (name "Net-(C3-Pad1)") (class "Default")
      (node (ref "C3") (pin "1") (pinfunction "1_1") (pintype "passive"))
      (node (ref "R35") (pin "2") (pinfunction "2_2") (pintype "passive"))
    )
    (net (code "28") (name "Net-(C16-+)") (class "Default")
      (node (ref "C16") (pin "POS") (pinfunction "+_POS") (pintype "passive"))
      (node (ref "C24") (pin "POS") (pinfunction "+_POS") (pintype "passive"))
      (node (ref "C28") (pin "POS") (pinfunction "+_POS") (pintype "passive"))
      (node (ref "D6") (pin "K") (pinfunction "C_K") (pintype "passive"))
      (node (ref "Q2") (pin "3") (pinfunction "D_3") (pintype "passive"))
      (node (ref "Q4") (pin "3") (pinfunction "D_3") (pintype "passive"))
    )
    (net (code "29") (name "Net-(D1-C)") (class "Default")
      (node (ref "D1") (pin "K") (pinfunction "C_K") (pintype "passive"))
      (node (ref "L1") (pin "1") (pinfunction "1_1") (pintype "passive"))
      (node (ref "U4") (pin "2") (pinfunction "SW_2") (pintype "power_in"))
    )
    (net (code "30") (name "Net-(D5-A)") (class "Default")
      (node (ref "C21") (pin "2") (pinfunction "2_2") (pintype "passive"))
      (node (ref "D5") (pin "1") (pinfunction "A_1") (pintype "passive"))
      (node (ref "Q6") (pin "G") (pinfunction "G_G") (pintype "passive"))
      (node (ref "R32") (pin "2") (pinfunction "2_2") (pintype "passive"))
    )
    (net (code "31") (name "Net-(F3-Pad1)") (class "Default")
      (node (ref "F3") (pin "1") (pinfunction "1_1") (pintype "passive"))
      (node (ref "L2") (pin "3") (pinfunction "3_3") (pintype "passive"))
    )
    (net (code "32") (name "Net-(IC1A-O)") (class "Default")
      (node (ref "IC1") (pin "4") (pinfunction "O_4") (pintype "open_collector"))
      (node (ref "R44") (pin "1") (pinfunction "1_1") (pintype "passive"))
      (node (ref "TP7") (pin "TP") (pinfunction "TP_TP") (pintype "input"))
      (node (ref "U3") (pin "3") (pinfunction "BLI_3") (pintype "bidirectional"))
    )
    (net (code "33") (name "Net-(IC2A-O)") (class "Default")
      (node (ref "IC2") (pin "4") (pinfunction "O_4") (pintype "open_collector"))
      (node (ref "R45") (pin "1") (pinfunction "1_1") (pintype "passive"))
      (node (ref "U3") (pin "8") (pinfunction "DIS_8") (pintype "bidirectional"))
    )
    (net (code "34") (name "Net-(LED1-PadC)") (class "Default")
      (node (ref "LED1") (pin "C") (pinfunction "C_C") (pintype "passive"))
      (node (ref "R29") (pin "2") (pinfunction "2_2") (pintype "passive"))
    )
    (net (code "35") (name "Net-(LED2-PadC)") (class "Default")
      (node (ref "LED2") (pin "C") (pinfunction "C_C") (pintype "passive"))
      (node (ref "R30") (pin "2") (pinfunction "2_2") (pintype "passive"))
    )
    (net (code "36") (name "Net-(LED3-PadC)") (class "Default")
      (node (ref "LED3") (pin "C") (pinfunction "C_C") (pintype "passive"))
      (node (ref "R31") (pin "2") (pinfunction "2_2") (pintype "passive"))
    )
    (net (code "37") (name "Net-(Q1-D)") (class "Default")
      (node (ref "Q1") (pin "3") (pinfunction "D_3") (pintype "passive"))
      (node (ref "X4") (pin "2") (pinfunction "KL_2") (pintype "passive"))
    )
    (net (code "38") (name "Net-(Q1-G)") (class "Default")
      (node (ref "Q1") (pin "1") (pinfunction "G_1") (pintype "passive"))
      (node (ref "R1") (pin "2") (pinfunction "2_2") (pintype "passive"))
      (node (ref "TP9") (pin "TP") (pinfunction "TP_TP") (pintype "input"))
    )
    (net (code "39") (name "Net-(Q2-G)") (class "Default")
      (node (ref "Q2") (pin "1") (pinfunction "G_1") (pintype "passive"))
      (node (ref "R40") (pin "2") (pinfunction "2_2") (pintype "passive"))
    )
    (net (code "40") (name "Net-(Q3-G)") (class "Default")
      (node (ref "Q3") (pin "1") (pinfunction "G_1") (pintype "passive"))
      (node (ref "R42") (pin "2") (pinfunction "2_2") (pintype "passive"))
    )
    (net (code "41") (name "Net-(Q3-S)") (class "Default")
      (node (ref "Q3") (pin "2") (pinfunction "S_2") (pintype "passive"))
      (node (ref "R25") (pin "2") (pinfunction "2_2") (pintype "passive"))
      (node (ref "R26") (pin "2") (pinfunction "2_2") (pintype "passive"))
    )
    (net (code "42") (name "Net-(Q4-G)") (class "Default")
      (node (ref "Q4") (pin "1") (pinfunction "G_1") (pintype "passive"))
      (node (ref "R41") (pin "1") (pinfunction "1_1") (pintype "passive"))
    )
    (net (code "43") (name "Net-(Q5-G)") (class "Default")
      (node (ref "Q5") (pin "1") (pinfunction "G_1") (pintype "passive"))
      (node (ref "R43") (pin "1") (pinfunction "1_1") (pintype "passive"))
    )
    (net (code "44") (name "Net-(Q5-S)") (class "Default")
      (node (ref "Q5") (pin "2") (pinfunction "S_2") (pintype "passive"))
      (node (ref "R27") (pin "2") (pinfunction "2_2") (pintype "passive"))
      (node (ref "R28") (pin "1") (pinfunction "1_1") (pintype "passive"))
    )
    (net (code "45") (name "Net-(T1-B)") (class "Default")
      (node (ref "R5") (pin "2") (pinfunction "2_2") (pintype "passive"))
      (node (ref "T1") (pin "1") (pinfunction "B_1") (pintype "passive"))
      (node (ref "TP10") (pin "TP") (pinfunction "TP_TP") (pintype "input"))
    )
    (net (code "46") (name "Net-(T1-C)") (class "Default")
      (node (ref "R2") (pin "1") (pinfunction "1_1") (pintype "passive"))
      (node (ref "R4") (pin "1") (pinfunction "1_1") (pintype "passive"))
      (node (ref "T1") (pin "3") (pinfunction "C_3") (pintype "passive"))
    )
    (net (code "47") (name "Net-(T2-B)") (class "Default")
      (node (ref "R4") (pin "2") (pinfunction "2_2") (pintype "passive"))
      (node (ref "T2") (pin "1") (pinfunction "B_1") (pintype "passive"))
      (node (ref "T3") (pin "B") (pinfunction "B_B") (pintype "passive"))
    )
    (net (code "48") (name "Net-(T2-E)") (class "Default")
      (node (ref "R1") (pin "1") (pinfunction "1_1") (pintype "passive"))
      (node (ref "T2") (pin "2") (pinfunction "E_2") (pintype "passive"))
      (node (ref "T3") (pin "E") (pinfunction "E_E") (pintype "passive"))
    )
    (net (code "49") (name "Net-(U3-AHB)") (class "Default")
      (node (ref "C15") (pin "1") (pinfunction "1_1") (pintype "passive"))
      (node (ref "D3") (pin "C") (pinfunction "C_C") (pintype "passive"))
      (node (ref "U3") (pin "9") (pinfunction "AHB_9") (pintype "bidirectional"))
    )
    (net (code "50") (name "Net-(U3-BHB)") (class "Default")
      (node (ref "C14") (pin "2") (pinfunction "2_2") (pintype "passive"))
      (node (ref "D2") (pin "C") (pinfunction "C_C") (pintype "passive"))
      (node (ref "U3") (pin "1") (pinfunction "BHB_1") (pintype "bidirectional"))
    )
    (net (code "51") (name "Net-(U3-DEL)") (class "Default")
      (node (ref "R24") (pin "2") (pinfunction "2_2") (pintype "passive"))
      (node (ref "U3") (pin "5") (pinfunction "DEL_5") (pintype "bidirectional"))
    )
    (net (code "52") (name "Net-(U4-SHDN)") (class "Default")
      (node (ref "R16") (pin "2") (pinfunction "2_2") (pintype "passive"))
      (node (ref "U4") (pin "5") (pinfunction "SHDN_5") (pintype "input"))
    )
    (net (code "53") (name "Net-(U5-ON{slash}_OFF)") (class "Default")
      (node (ref "R18") (pin "2") (pinfunction "2_2") (pintype "passive"))
      (node (ref "U5") (pin "3") (pinfunction "ON/_OFF_3") (pintype "input"))
    )
    (net (code "54") (name "Net-(U6-A3)") (class "Default")
      (node (ref "TP2") (pin "TP") (pinfunction "TP_TP") (pintype "input"))
      (node (ref "U6") (pin "10") (pinfunction "A3_10") (pintype "input"))
    )
    (net (code "55") (name "Net-(U6-ADDR)") (class "Default")
      (node (ref "R19") (pin "2") (pinfunction "2_2") (pintype "passive"))
      (node (ref "U6") (pin "5") (pinfunction "ADDR_5") (pintype "input"))
    )
    (net (code "56") (name "Net-(U7-VDD)") (class "Default")
      (node (ref "C12") (pin "1") (pinfunction "1_1") (pintype "passive"))
      (node (ref "C13") (pin "1") (pinfunction "1_1") (pintype "passive"))
      (node (ref "R22") (pin "2") (pinfunction "2_2") (pintype "passive"))
      (node (ref "U7") (pin "P$2") (pinfunction "VDD_P$2") (pintype "power_in"))
    )
    (net (code "57") (name "Net-(U9-ADDR)") (class "Default")
      (node (ref "R39") (pin "1") (pinfunction "1_1") (pintype "passive"))
      (node (ref "U9") (pin "1") (pinfunction "ADDR_1") (pintype "input"))
    )
    (net (code "58") (name "Net-(U9-AIN3)") (class "Default")
      (node (ref "TP13") (pin "TP") (pinfunction "TP_TP") (pintype "input"))
      (node (ref "U9") (pin "7") (pinfunction "AIN3_7") (pintype "input"))
    )
    (net (code "59") (name "Net-(U9-ALERT)") (class "Default")
      (node (ref "TP12") (pin "TP") (pinfunction "TP_TP") (pintype "input"))
      (node (ref "U9") (pin "2") (pinfunction "ALERT_2") (pintype "output"))
    )
    (net (code "60") (name "Net-(X1A-KL)") (class "Default")
      (node (ref "L2") (pin "1") (pinfunction "1_1") (pintype "passive"))
      (node (ref "X1") (pin "1") (pinfunction "KL_1") (pintype "passive"))
    )
    (net (code "61") (name "Net-(X1B-KL)") (class "Default")
      (node (ref "L2") (pin "2") (pinfunction "2_2") (pintype "passive"))
      (node (ref "X1") (pin "2") (pinfunction "KL_2") (pintype "passive"))
    )
    (net (code "62") (name "SCL") (class "Default")
      (node (ref "R20") (pin "1") (pinfunction "1_1") (pintype "passive"))
      (node (ref "U2") (pin "29") (pinfunction "GPIO5_29") (pintype "bidirectional"))
      (node (ref "U6") (pin "3") (pinfunction "SCL_3") (pintype "bidirectional"))
      (node (ref "U7") (pin "P$1") (pinfunction "SCL_P$1") (pintype "bidirectional"))
      (node (ref "U9") (pin "10") (pinfunction "SCL_10") (pintype "bidirectional"))
    )
    (net (code "63") (name "SDA") (class "Default")
      (node (ref "R21") (pin "1") (pinfunction "1_1") (pintype "passive"))
      (node (ref "U2") (pin "28") (pinfunction "GPIO4_28") (pintype "bidirectional"))
      (node (ref "U6") (pin "4") (pinfunction "SDA_4") (pintype "bidirectional"))
      (node (ref "U7") (pin "P$4") (pinfunction "SDA_P$4") (pintype "bidirectional"))
      (node (ref "U9") (pin "9") (pinfunction "SDA_9") (pintype "bidirectional"))
    )
    (net (code "64") (name "unconnected-(U1-PadNULL)") (class "Default")
      (node (ref "U1") (pin "NULL") (pinfunction "NULL_NULL") (pintype "no_connect"))
    )
    (net (code "65") (name "unconnected-(U2-CS{slash}SDCMD-Pad7)") (class "Default")
      (node (ref "U2") (pin "7") (pinfunction "CS/SDCMD_7") (pintype "bidirectional"))
    )
    (net (code "66") (name "unconnected-(U2-EN-Pad12)") (class "Default")
      (node (ref "U2") (pin "12") (pinfunction "EN_12") (pintype "bidirectional"))
    )
    (net (code "67") (name "unconnected-(U2-GPIO9{slash}SDD2-Pad5)") (class "Default")
      (node (ref "U2") (pin "5") (pinfunction "GPIO9/SDD2_5") (pintype "bidirectional"))
    )
    (net (code "68") (name "unconnected-(U2-GPIO10{slash}SDD3-Pad4)") (class "Default")
      (node (ref "U2") (pin "4") (pinfunction "GPIO10/SDD3_4") (pintype "bidirectional"))
    )
    (net (code "69") (name "unconnected-(U2-MISO{slash}SDD0-Pad8)") (class "Default")
      (node (ref "U2") (pin "8") (pinfunction "MISO/SDD0_8") (pintype "bidirectional"))
    )
    (net (code "70") (name "unconnected-(U2-MOSI{slash}SDD1-Pad6)") (class "Default")
      (node (ref "U2") (pin "6") (pinfunction "MOSI/SDD1_6") (pintype "bidirectional"))
    )
    (net (code "71") (name "unconnected-(U2-RST-Pad13)") (class "Default")
      (node (ref "U2") (pin "13") (pinfunction "RST_13") (pintype "bidirectional"))
    )
    (net (code "72") (name "unconnected-(U2-RSV0-Pad2)") (class "Default")
      (node (ref "U2") (pin "2") (pinfunction "RSV0_2") (pintype "no_connect"))
    )
    (net (code "73") (name "unconnected-(U2-RSV1-Pad3)") (class "Default")
      (node (ref "U2") (pin "3") (pinfunction "RSV1_3") (pintype "no_connect"))
    )
    (net (code "74") (name "unconnected-(U2-SCLK{slash}SDCLK-Pad9)") (class "Default")
      (node (ref "U2") (pin "9") (pinfunction "SCLK/SDCLK_9") (pintype "bidirectional"))
    )
    (net (code "75") (name "unconnected-(U5-NC-Pad4)") (class "Default")
      (node (ref "U5") (pin "4") (pinfunction "NC_4") (pintype "no_connect"))
    )
    (net (code "76") (name "unconnected-(U6-ALRT-Pad6)") (class "Default")
      (node (ref "U6") (pin "6") (pinfunction "ALRT_6") (pintype "output"))
    )
  )
)
